# relay_controller.net
KiCad netlist of a schematic drawn in EAGLE
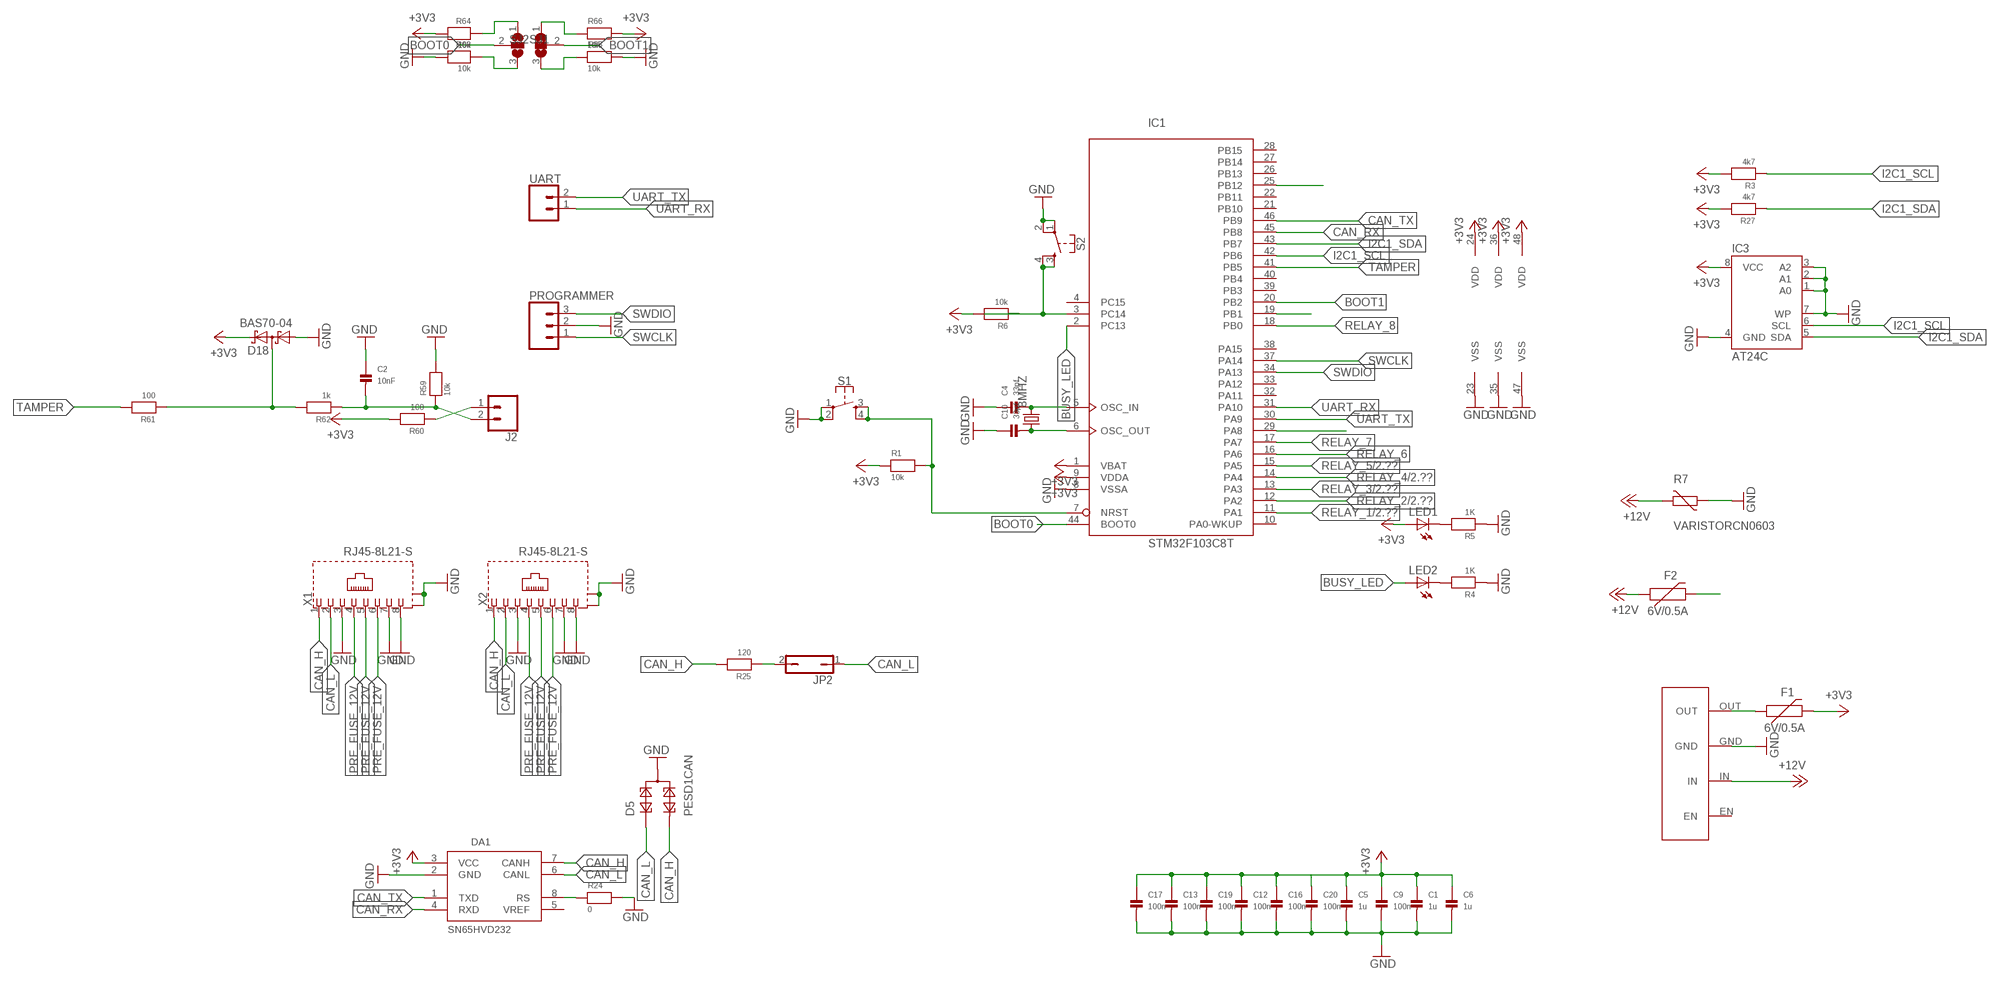
[diagram p0: schematic, sheet 1]
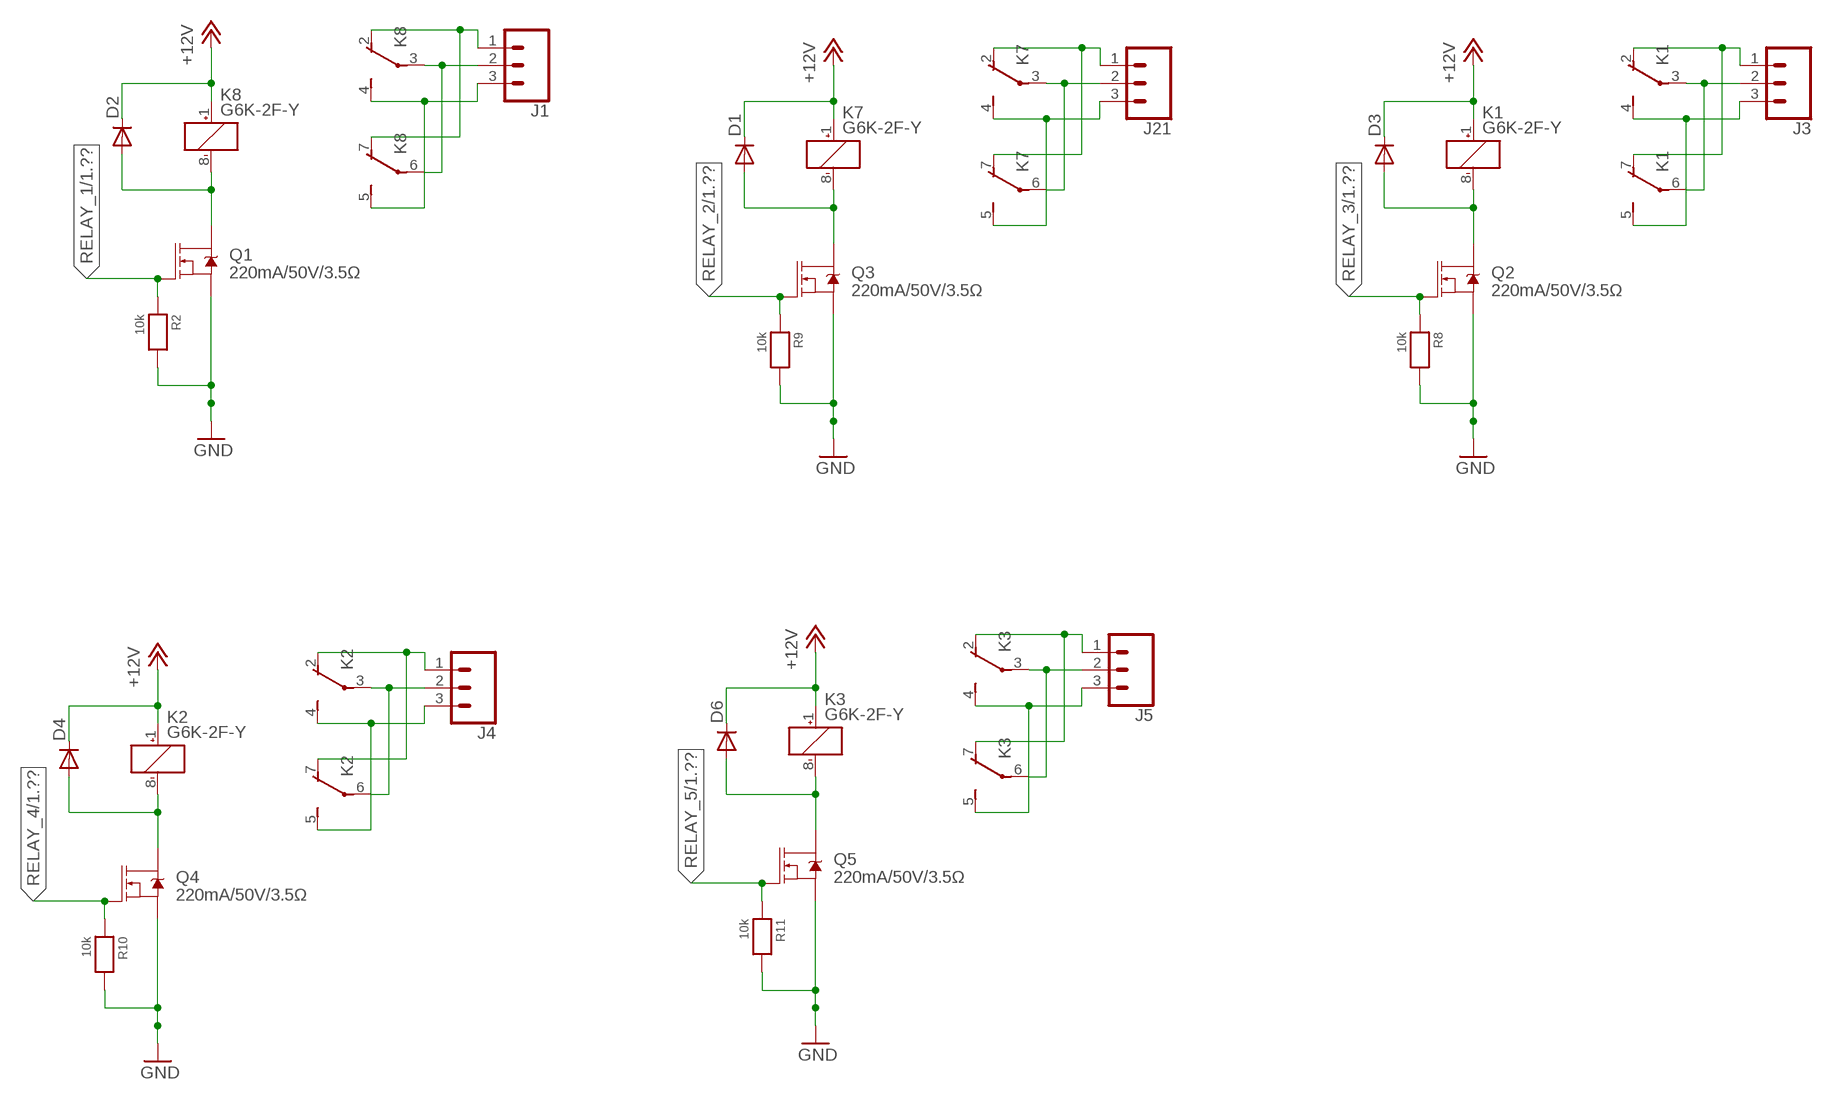
[diagram p1: schematic, sheet 2]

(export (version "E")
  (design (tool "Eeschema 10.0.6"))
  (components
    (comp (ref "D1")
      (value "DIODE-DO-214AC")
      (footprint "eagle-import:DO-214AC")
      (libsource (lib "eagle-import") (part "DIODE-DO-214AC"))
    )
    (comp (ref "D2")
      (value "DIODE-DO-214AC")
      (footprint "eagle-import:DO-214AC")
      (libsource (lib "eagle-import") (part "DIODE-DO-214AC"))
    )
    (comp (ref "D3")
      (value "DIODE-DO-214AC")
      (footprint "eagle-import:DO-214AC")
      (libsource (lib "eagle-import") (part "DIODE-DO-214AC"))
    )
    (comp (ref "D4")
      (value "DIODE-DO-214AC")
      (footprint "eagle-import:DO-214AC")
      (libsource (lib "eagle-import") (part "DIODE-DO-214AC"))
    )
    (comp (ref "D6")
      (value "DIODE-DO-214AC")
      (footprint "eagle-import:DO-214AC")
      (libsource (lib "eagle-import") (part "DIODE-DO-214AC"))
    )
    (comp (ref "J1")
      (value "CONN_03SCREW")
      (footprint "eagle-import:SCREWTERMINAL-3.5MM-3")
      (libsource (lib "eagle-import") (part "CONN_03SCREW"))
    )
    (comp (ref "J3")
      (value "CONN_03SCREW")
      (footprint "eagle-import:SCREWTERMINAL-3.5MM-3")
      (libsource (lib "eagle-import") (part "CONN_03SCREW"))
    )
    (comp (ref "J4")
      (value "CONN_03SCREW")
      (footprint "eagle-import:SCREWTERMINAL-3.5MM-3")
      (libsource (lib "eagle-import") (part "CONN_03SCREW"))
    )
    (comp (ref "J5")
      (value "CONN_03SCREW")
      (footprint "eagle-import:SCREWTERMINAL-3.5MM-3")
      (libsource (lib "eagle-import") (part "CONN_03SCREW"))
    )
    (comp (ref "J21")
      (value "CONN_03SCREW")
      (footprint "eagle-import:SCREWTERMINAL-3.5MM-3")
      (libsource (lib "eagle-import") (part "CONN_03SCREW"))
    )
    (comp (ref "K1")
      (value "G6K-2F-Y")
      (footprint "eagle-import:G6K-2F-Y")
      (fields (field (name "MF") "OMRON COMPONENTS USA") (field (name "MPN") "G6K-2F-Y DC3"))
      (libsource (lib "eagle-import") (part "G6K-2F-Y"))
    )
    (comp (ref "K2")
      (value "G6K-2F-Y")
      (footprint "eagle-import:G6K-2F-Y")
      (fields (field (name "MF") "OMRON COMPONENTS USA") (field (name "MPN") "G6K-2F-Y DC3"))
      (libsource (lib "eagle-import") (part "G6K-2F-Y"))
    )
    (comp (ref "K3")
      (value "G6K-2F-Y")
      (footprint "eagle-import:G6K-2F-Y")
      (fields (field (name "MF") "OMRON COMPONENTS USA") (field (name "MPN") "G6K-2F-Y DC3"))
      (libsource (lib "eagle-import") (part "G6K-2F-Y"))
    )
    (comp (ref "K7")
      (value "G6K-2F-Y")
      (footprint "eagle-import:G6K-2F-Y")
      (fields (field (name "MF") "OMRON COMPONENTS USA") (field (name "MPN") "G6K-2F-Y DC3"))
      (libsource (lib "eagle-import") (part "G6K-2F-Y"))
    )
    (comp (ref "K8")
      (value "G6K-2F-Y")
      (footprint "eagle-import:G6K-2F-Y")
      (fields (field (name "MF") "OMRON COMPONENTS USA") (field (name "MPN") "G6K-2F-Y DC3"))
      (libsource (lib "eagle-import") (part "G6K-2F-Y"))
    )
    (comp (ref "Q1")
      (value "220mA/50V/3.5Ω")
      (footprint "eagle-import:SOT23-3")
      (libsource (lib "eagle-import") (part "MOSFET-NCH-BSS138"))
    )
    (comp (ref "Q2")
      (value "220mA/50V/3.5Ω")
      (footprint "eagle-import:SOT23-3")
      (libsource (lib "eagle-import") (part "MOSFET-NCH-BSS138"))
    )
    (comp (ref "Q3")
      (value "220mA/50V/3.5Ω")
      (footprint "eagle-import:SOT23-3")
      (libsource (lib "eagle-import") (part "MOSFET-NCH-BSS138"))
    )
    (comp (ref "Q4")
      (value "220mA/50V/3.5Ω")
      (footprint "eagle-import:SOT23-3")
      (libsource (lib "eagle-import") (part "MOSFET-NCH-BSS138"))
    )
    (comp (ref "Q5")
      (value "220mA/50V/3.5Ω")
      (footprint "eagle-import:SOT23-3")
      (libsource (lib "eagle-import") (part "MOSFET-NCH-BSS138"))
    )
    (comp (ref "R2")
      (value "10k")
      (footprint "eagle-import:0603")
      (libsource (lib "eagle-import") (part "RESISTOR0603"))
    )
    (comp (ref "R8")
      (value "10k")
      (footprint "eagle-import:0603")
      (libsource (lib "eagle-import") (part "RESISTOR0603"))
    )
    (comp (ref "R9")
      (value "10k")
      (footprint "eagle-import:0603")
      (libsource (lib "eagle-import") (part "RESISTOR0603"))
    )
    (comp (ref "R10")
      (value "10k")
      (footprint "eagle-import:0603")
      (libsource (lib "eagle-import") (part "RESISTOR0603"))
    )
    (comp (ref "R11")
      (value "10k")
      (footprint "eagle-import:0603")
      (libsource (lib "eagle-import") (part "RESISTOR0603"))
    )
    (comp (ref "8MHZ")
      (value "CRYSTALHC49UP")
      (footprint "eagle-import:HC49UP")
      (libsource (lib "eagle-import") (part "CRYSTALHC49UP"))
    )
    (comp (ref "C1")
      (value "1u")
      (footprint "eagle-import:0603")
      (libsource (lib "eagle-import") (part "CAP_CERAMIC0603"))
    )
    (comp (ref "C2")
      (value "10nF")
      (footprint "eagle-import:0603")
      (libsource (lib "eagle-import") (part "CAP_CERAMIC0603"))
    )
    (comp (ref "C4")
      (value "33pf")
      (footprint "eagle-import:0603")
      (libsource (lib "eagle-import") (part "CAP_CERAMIC0603"))
    )
    (comp (ref "C5")
      (value "1u")
      (footprint "eagle-import:0603")
      (libsource (lib "eagle-import") (part "CAP_CERAMIC0603"))
    )
    (comp (ref "C6")
      (value "1u")
      (footprint "eagle-import:0603")
      (libsource (lib "eagle-import") (part "CAP_CERAMIC0603"))
    )
    (comp (ref "C9")
      (value "100n")
      (footprint "eagle-import:0603")
      (libsource (lib "eagle-import") (part "CAP_CERAMIC0603"))
    )
    (comp (ref "C10")
      (value "33pf")
      (footprint "eagle-import:0603")
      (libsource (lib "eagle-import") (part "CAP_CERAMIC0603"))
    )
    (comp (ref "C12")
      (value "100n")
      (footprint "eagle-import:0603")
      (libsource (lib "eagle-import") (part "CAP_CERAMIC0603"))
    )
    (comp (ref "C13")
      (value "100n")
      (footprint "eagle-import:0603")
      (libsource (lib "eagle-import") (part "CAP_CERAMIC0603"))
    )
    (comp (ref "C16")
      (value "100n")
      (footprint "eagle-import:0603")
      (libsource (lib "eagle-import") (part "CAP_CERAMIC0603"))
    )
    (comp (ref "C17")
      (value "100n")
      (footprint "eagle-import:0603")
      (libsource (lib "eagle-import") (part "CAP_CERAMIC0603"))
    )
    (comp (ref "C19")
      (value "100n")
      (footprint "eagle-import:0603")
      (libsource (lib "eagle-import") (part "CAP_CERAMIC0603"))
    )
    (comp (ref "C20")
      (value "100n")
      (footprint "eagle-import:0603")
      (libsource (lib "eagle-import") (part "CAP_CERAMIC0603"))
    )
    (comp (ref "D5")
      (value "PESD1CAN")
      (footprint "eagle-import:SOT23")
      (libsource (lib "eagle-import") (part "PESD1CAN"))
    )
    (comp (ref "D18")
      (value "BAS70-04")
      (footprint "eagle-import:SOT23")
      (libsource (lib "eagle-import") (part "BAS70-04"))
    )
    (comp (ref "DA1")
      (value "SN65HVD232")
      (footprint "eagle-import:SO08")
      (libsource (lib "eagle-import") (part "SN65HVD232"))
    )
    (comp (ref "F1")
      (value "6V/0.5A")
      (footprint "eagle-import:1206")
      (libsource (lib "eagle-import") (part "PPTC_HALF-AMP"))
    )
    (comp (ref "F2")
      (value "6V/0.5A")
      (footprint "eagle-import:1206")
      (libsource (lib "eagle-import") (part "PPTC_HALF-AMP"))
    )
    (comp (ref "IC1")
      (value "STM32F103C8T")
      (footprint "eagle-import:LQFP48")
      (libsource (lib "eagle-import") (part "STM32F103CT8"))
    )
    (comp (ref "IC3")
      (value "AT24C")
      (footprint "eagle-import:SOIC8")
      (libsource (lib "eagle-import") (part "AT24C"))
    )
    (comp (ref "J2")
      (value "CONN_023.5MM")
      (footprint "eagle-import:SCREWTERMINAL-3.5MM-2")
      (libsource (lib "eagle-import") (part "CONN_023.5MM"))
    )
    (comp (ref "JP2")
      (value "JP1Q")
      (footprint "eagle-import:JP1")
      (libsource (lib "eagle-import") (part "JP1Q"))
    )
    (comp (ref "LED1")
      (value "LEDCHIPLED_0805")
      (footprint "eagle-import:CHIPLED_0805")
      (libsource (lib "eagle-import") (part "LEDCHIPLED_0805"))
    )
    (comp (ref "LED2")
      (value "LEDCHIPLED_0805")
      (footprint "eagle-import:CHIPLED_0805")
      (libsource (lib "eagle-import") (part "LEDCHIPLED_0805"))
    )
    (comp (ref "PROGRAMMER")
      (value "CONN_03LOCK")
      (footprint "eagle-import:1X03_LOCK")
      (libsource (lib "eagle-import") (part "CONN_03LOCK"))
    )
    (comp (ref "R1")
      (value "10k")
      (footprint "eagle-import:0603")
      (libsource (lib "eagle-import") (part "RESISTOR0603"))
    )
    (comp (ref "R3")
      (value "4k7")
      (footprint "eagle-import:0603")
      (libsource (lib "eagle-import") (part "RESISTOR0603"))
    )
    (comp (ref "R4")
      (value "1K")
      (footprint "eagle-import:0603")
      (libsource (lib "eagle-import") (part "RESISTOR0603"))
    )
    (comp (ref "R5")
      (value "1K")
      (footprint "eagle-import:0603")
      (libsource (lib "eagle-import") (part "RESISTOR0603"))
    )
    (comp (ref "R6")
      (value "10k")
      (footprint "eagle-import:0603")
      (libsource (lib "eagle-import") (part "RESISTOR0603"))
    )
    (comp (ref "R7")
      (value "VARISTORCN0603")
      (footprint "eagle-import:CT_CN0603")
      (libsource (lib "eagle-import") (part "VARISTORCN0603"))
    )
    (comp (ref "R24")
      (value "0")
      (footprint "eagle-import:0603")
      (libsource (lib "eagle-import") (part "RESISTOR0603"))
    )
    (comp (ref "R25")
      (value "120")
      (footprint "eagle-import:0603")
      (libsource (lib "eagle-import") (part "RESISTOR0603"))
    )
    (comp (ref "R27")
      (value "4k7")
      (footprint "eagle-import:0603")
      (libsource (lib "eagle-import") (part "RESISTOR0603"))
    )
    (comp (ref "R59")
      (value "10k")
      (footprint "eagle-import:0603")
      (libsource (lib "eagle-import") (part "RESISTOR0603"))
    )
    (comp (ref "R60")
      (value "100")
      (footprint "eagle-import:0603")
      (libsource (lib "eagle-import") (part "RESISTOR0603"))
    )
    (comp (ref "R61")
      (value "100")
      (footprint "eagle-import:0603")
      (libsource (lib "eagle-import") (part "RESISTOR0603"))
    )
    (comp (ref "R62")
      (value "1k")
      (footprint "eagle-import:0603")
      (libsource (lib "eagle-import") (part "RESISTOR0603"))
    )
    (comp (ref "R63")
      (value "10k")
      (footprint "eagle-import:0603")
      (libsource (lib "eagle-import") (part "RESISTOR0603"))
    )
    (comp (ref "R64")
      (value "10k")
      (footprint "eagle-import:0603")
      (libsource (lib "eagle-import") (part "RESISTOR0603"))
    )
    (comp (ref "R65")
      (value "10k")
      (footprint "eagle-import:0603")
      (libsource (lib "eagle-import") (part "RESISTOR0603"))
    )
    (comp (ref "R66")
      (value "10k")
      (footprint "eagle-import:0603")
      (libsource (lib "eagle-import") (part "RESISTOR0603"))
    )
    (comp (ref "S1")
      (value "MOMENTARY-SWITCH-SPST-2-SMD-4.6X2.8MM")
      (footprint "eagle-import:TACTILE_SWITCH_SMD_4.6X2.8MM")
      (libsource (lib "eagle-import") (part "MOMENTARY-SWITCH-SPST-2-SMD-4.6X2.8MM"))
    )
    (comp (ref "S2")
      (value "MOMENTARY-SWITCH-SPST-2-SMD-4.6X2.8MM")
      (footprint "eagle-import:TACTILE_SWITCH_SMD_4.6X2.8MM")
      (libsource (lib "eagle-import") (part "MOMENTARY-SWITCH-SPST-2-SMD-4.6X2.8MM"))
    )
    (comp (ref "SJ1")
      (value "SJ2W")
      (footprint "eagle-import:SJ_2")
      (libsource (lib "eagle-import") (part "SJ2W"))
    )
    (comp (ref "SJ2")
      (value "SJ2W")
      (footprint "eagle-import:SJ_2")
      (libsource (lib "eagle-import") (part "SJ2W"))
    )
    (comp (ref "U$1")
      (value "HW-613")
      (footprint "eagle-import:HW-613")
      (libsource (lib "eagle-import") (part "HW-613"))
    )
    (comp (ref "UART")
      (value "CONN_02")
      (footprint "eagle-import:1X02")
      (libsource (lib "eagle-import") (part "CONN_02"))
    )
    (comp (ref "X1")
      (value "RJ45-8L21-S")
      (footprint "eagle-import:RJ45-SHIELD1")
      (libsource (lib "eagle-import") (part "RJ4521-S-8L"))
    )
    (comp (ref "X2")
      (value "RJ45-8L21-S")
      (footprint "eagle-import:RJ45-SHIELD1")
      (libsource (lib "eagle-import") (part "RJ4521-S-8L"))
    )
  )
  (nets
    (net (code "1") (name "+3V3") (class "Default")
      (node (ref "C1") (pin "1") (pinfunction "P$1_1") (pintype "passive"))
      (node (ref "C12") (pin "1") (pinfunction "P$1_1") (pintype "passive"))
      (node (ref "C13") (pin "1") (pinfunction "P$1_1") (pintype "passive"))
      (node (ref "C16") (pin "1") (pinfunction "P$1_1") (pintype "passive"))
      (node (ref "C17") (pin "1") (pinfunction "P$1_1") (pintype "passive"))
      (node (ref "C19") (pin "1") (pinfunction "P$1_1") (pintype "passive"))
      (node (ref "C20") (pin "1") (pinfunction "P$1_1") (pintype "passive"))
      (node (ref "C5") (pin "1") (pinfunction "P$1_1") (pintype "passive"))
      (node (ref "C6") (pin "1") (pinfunction "P$1_1") (pintype "passive"))
      (node (ref "C9") (pin "1") (pinfunction "P$1_1") (pintype "passive"))
      (node (ref "D18") (pin "2") (pinfunction "C2_2") (pintype "passive"))
      (node (ref "DA1") (pin "3") (pinfunction "VCC_3") (pintype "power_in"))
      (node (ref "F1") (pin "2") (pinfunction "2_2") (pintype "bidirectional"))
      (node (ref "IC1") (pin "1") (pinfunction "VBAT_1") (pintype "power_in"))
      (node (ref "IC1") (pin "24") (pinfunction "VDD_24") (pintype "power_in"))
      (node (ref "IC1") (pin "36") (pinfunction "VDD_36") (pintype "power_in"))
      (node (ref "IC1") (pin "48") (pinfunction "VDD_48") (pintype "power_in"))
      (node (ref "IC1") (pin "9") (pinfunction "VDDA_9") (pintype "power_in"))
      (node (ref "IC3") (pin "8") (pinfunction "VCC_8") (pintype "power_in"))
      (node (ref "LED1") (pin "A") (pinfunction "A_A") (pintype "passive"))
      (node (ref "R1") (pin "1") (pinfunction "1_1") (pintype "passive"))
      (node (ref "R27") (pin "2") (pinfunction "2_2") (pintype "passive"))
      (node (ref "R3") (pin "2") (pinfunction "2_2") (pintype "passive"))
      (node (ref "R6") (pin "2") (pinfunction "2_2") (pintype "passive"))
      (node (ref "R60") (pin "2") (pinfunction "2_2") (pintype "passive"))
      (node (ref "R64") (pin "2") (pinfunction "2_2") (pintype "passive"))
      (node (ref "R66") (pin "2") (pinfunction "2_2") (pintype "passive"))
    )
    (net (code "2") (name "+12V") (class "Default")
      (node (ref "D1") (pin "C") (pinfunction "C_C") (pintype "passive"))
      (node (ref "D2") (pin "C") (pinfunction "C_C") (pintype "passive"))
      (node (ref "D3") (pin "C") (pinfunction "C_C") (pintype "passive"))
      (node (ref "D4") (pin "C") (pinfunction "C_C") (pintype "passive"))
      (node (ref "D6") (pin "C") (pinfunction "C_C") (pintype "passive"))
      (node (ref "F2") (pin "1") (pinfunction "1_1") (pintype "bidirectional"))
      (node (ref "K1") (pin "1") (pinfunction "+_1") (pintype "passive"))
      (node (ref "K2") (pin "1") (pinfunction "+_1") (pintype "passive"))
      (node (ref "K3") (pin "1") (pinfunction "+_1") (pintype "passive"))
      (node (ref "K7") (pin "1") (pinfunction "+_1") (pintype "passive"))
      (node (ref "K8") (pin "1") (pinfunction "+_1") (pintype "passive"))
      (node (ref "R7") (pin "2") (pinfunction "2_2") (pintype "passive"))
      (node (ref "U$1") (pin "IN") (pinfunction "IN_IN") (pintype "bidirectional"))
    )
    (net (code "3") (name "BOOT0") (class "Default")
      (node (ref "IC1") (pin "44") (pinfunction "BOOT0_44") (pintype "input"))
      (node (ref "SJ1") (pin "2") (pinfunction "2_2") (pintype "passive"))
    )
    (net (code "4") (name "BOOT1") (class "Default")
      (node (ref "IC1") (pin "20") (pinfunction "PB2_20") (pintype "bidirectional"))
      (node (ref "SJ2") (pin "2") (pinfunction "2_2") (pintype "passive"))
    )
    (net (code "5") (name "BUSY_LED") (class "Default")
      (node (ref "IC1") (pin "2") (pinfunction "PC13_2") (pintype "bidirectional"))
      (node (ref "LED2") (pin "A") (pinfunction "A_A") (pintype "passive"))
    )
    (net (code "6") (name "CAN_H") (class "Default")
      (node (ref "D5") (pin "2") (pinfunction "2_2") (pintype "passive"))
      (node (ref "DA1") (pin "7") (pinfunction "CANH_7") (pintype "bidirectional"))
      (node (ref "R25") (pin "2") (pinfunction "2_2") (pintype "passive"))
      (node (ref "X1") (pin "1") (pinfunction "1_1") (pintype "passive"))
      (node (ref "X2") (pin "1") (pinfunction "1_1") (pintype "passive"))
    )
    (net (code "7") (name "CAN_L") (class "Default")
      (node (ref "D5") (pin "1") (pinfunction "1_1") (pintype "passive"))
      (node (ref "DA1") (pin "6") (pinfunction "CANL_6") (pintype "bidirectional"))
      (node (ref "JP2") (pin "1") (pinfunction "1_1") (pintype "passive"))
      (node (ref "X1") (pin "2") (pinfunction "2_2") (pintype "passive"))
      (node (ref "X2") (pin "2") (pinfunction "2_2") (pintype "passive"))
    )
    (net (code "8") (name "CAN_RX") (class "Default")
      (node (ref "DA1") (pin "4") (pinfunction "RXD_4") (pintype "output"))
      (node (ref "IC1") (pin "45") (pinfunction "PB8_45") (pintype "bidirectional"))
    )
    (net (code "9") (name "CAN_TX") (class "Default")
      (node (ref "DA1") (pin "1") (pinfunction "TXD_1") (pintype "input"))
      (node (ref "IC1") (pin "46") (pinfunction "PB9_46") (pintype "bidirectional"))
    )
    (net (code "10") (name "GND") (class "Default")
      (node (ref "C1") (pin "2") (pinfunction "P$2_2") (pintype "passive"))
      (node (ref "C10") (pin "1") (pinfunction "P$1_1") (pintype "passive"))
      (node (ref "C12") (pin "2") (pinfunction "P$2_2") (pintype "passive"))
      (node (ref "C13") (pin "2") (pinfunction "P$2_2") (pintype "passive"))
      (node (ref "C16") (pin "2") (pinfunction "P$2_2") (pintype "passive"))
      (node (ref "C17") (pin "2") (pinfunction "P$2_2") (pintype "passive"))
      (node (ref "C19") (pin "2") (pinfunction "P$2_2") (pintype "passive"))
      (node (ref "C2") (pin "1") (pinfunction "P$1_1") (pintype "passive"))
      (node (ref "C20") (pin "2") (pinfunction "P$2_2") (pintype "passive"))
      (node (ref "C4") (pin "1") (pinfunction "P$1_1") (pintype "passive"))
      (node (ref "C5") (pin "2") (pinfunction "P$2_2") (pintype "passive"))
      (node (ref "C6") (pin "2") (pinfunction "P$2_2") (pintype "passive"))
      (node (ref "C9") (pin "2") (pinfunction "P$2_2") (pintype "passive"))
      (node (ref "D18") (pin "1") (pinfunction "A1_1") (pintype "passive"))
      (node (ref "D5") (pin "3") (pinfunction "3_3") (pintype "passive"))
      (node (ref "DA1") (pin "2") (pinfunction "GND_2") (pintype "power_in"))
      (node (ref "IC1") (pin "23") (pinfunction "VSS_23") (pintype "power_in"))
      (node (ref "IC1") (pin "35") (pinfunction "VSS_35") (pintype "power_in"))
      (node (ref "IC1") (pin "47") (pinfunction "VSS_47") (pintype "power_in"))
      (node (ref "IC1") (pin "8") (pinfunction "VSSA_8") (pintype "power_in"))
      (node (ref "IC3") (pin "1") (pinfunction "A0_1") (pintype "input"))
      (node (ref "IC3") (pin "2") (pinfunction "A1_2") (pintype "input"))
      (node (ref "IC3") (pin "3") (pinfunction "A2_3") (pintype "input"))
      (node (ref "IC3") (pin "4") (pinfunction "GND_4") (pintype "power_in"))
      (node (ref "IC3") (pin "7") (pinfunction "WP_7") (pintype "input"))
      (node (ref "PROGRAMMER") (pin "2") (pinfunction "2_2") (pintype "passive"))
      (node (ref "Q1") (pin "2") (pinfunction "S_2") (pintype "bidirectional"))
      (node (ref "Q2") (pin "2") (pinfunction "S_2") (pintype "bidirectional"))
      (node (ref "Q3") (pin "2") (pinfunction "S_2") (pintype "bidirectional"))
      (node (ref "Q4") (pin "2") (pinfunction "S_2") (pintype "bidirectional"))
      (node (ref "Q5") (pin "2") (pinfunction "S_2") (pintype "bidirectional"))
      (node (ref "R10") (pin "2") (pinfunction "2_2") (pintype "passive"))
      (node (ref "R11") (pin "2") (pinfunction "2_2") (pintype "passive"))
      (node (ref "R2") (pin "2") (pinfunction "2_2") (pintype "passive"))
      (node (ref "R24") (pin "2") (pinfunction "2_2") (pintype "passive"))
      (node (ref "R4") (pin "1") (pinfunction "1_1") (pintype "passive"))
      (node (ref "R5") (pin "1") (pinfunction "1_1") (pintype "passive"))
      (node (ref "R59") (pin "2") (pinfunction "2_2") (pintype "passive"))
      (node (ref "R63") (pin "2") (pinfunction "2_2") (pintype "passive"))
      (node (ref "R65") (pin "2") (pinfunction "2_2") (pintype "passive"))
      (node (ref "R7") (pin "1") (pinfunction "1_1") (pintype "passive"))
      (node (ref "R8") (pin "2") (pinfunction "2_2") (pintype "passive"))
      (node (ref "R9") (pin "2") (pinfunction "2_2") (pintype "passive"))
      (node (ref "S1") (pin "1") (pinfunction "1_1") (pintype "passive"))
      (node (ref "S1") (pin "2") (pinfunction "2_2") (pintype "passive"))
      (node (ref "S2") (pin "1") (pinfunction "1_1") (pintype "passive"))
      (node (ref "S2") (pin "2") (pinfunction "2_2") (pintype "passive"))
      (node (ref "U$1") (pin "GND") (pinfunction "GND_GND") (pintype "bidirectional"))
      (node (ref "X1") (pin "3") (pinfunction "3_3") (pintype "passive"))
      (node (ref "X1") (pin "7") (pinfunction "7_7") (pintype "passive"))
      (node (ref "X1") (pin "8") (pinfunction "8_8") (pintype "passive"))
      (node (ref "X1") (pin "S1") (pinfunction "S_S1") (pintype "passive"))
      (node (ref "X1") (pin "S2") (pinfunction "S_S2") (pintype "passive"))
      (node (ref "X2") (pin "3") (pinfunction "3_3") (pintype "passive"))
      (node (ref "X2") (pin "7") (pinfunction "7_7") (pintype "passive"))
      (node (ref "X2") (pin "8") (pinfunction "8_8") (pintype "passive"))
      (node (ref "X2") (pin "S1") (pinfunction "S_S1") (pintype "passive"))
      (node (ref "X2") (pin "S2") (pinfunction "S_S2") (pintype "passive"))
    )
    (net (code "11") (name "I2C1_SCL") (class "Default")
      (node (ref "IC1") (pin "42") (pinfunction "PB6_42") (pintype "bidirectional"))
      (node (ref "IC3") (pin "6") (pinfunction "SCL_6") (pintype "bidirectional"))
      (node (ref "R3") (pin "1") (pinfunction "1_1") (pintype "passive"))
    )
    (net (code "12") (name "I2C1_SDA") (class "Default")
      (node (ref "IC1") (pin "43") (pinfunction "PB7_43") (pintype "bidirectional"))
      (node (ref "IC3") (pin "5") (pinfunction "SDA_5") (pintype "bidirectional"))
      (node (ref "R27") (pin "1") (pinfunction "1_1") (pintype "passive"))
    )
    (net (code "13") (name "Net-(C2-P$2)") (class "Default")
      (node (ref "C2") (pin "2") (pinfunction "P$2_2") (pintype "passive"))
      (node (ref "J2") (pin "2") (pinfunction "2_2") (pintype "passive"))
      (node (ref "R59") (pin "1") (pinfunction "1_1") (pintype "passive"))
      (node (ref "R62") (pin "1") (pinfunction "1_1") (pintype "passive"))
    )
    (net (code "14") (name "Net-(C4-P$2)") (class "Default")
      (node (ref "8MHZ") (pin "2") (pinfunction "2_2") (pintype "passive"))
      (node (ref "C4") (pin "2") (pinfunction "P$2_2") (pintype "passive"))
      (node (ref "IC1") (pin "5") (pinfunction "OSC_IN_5") (pintype "bidirectional"))
    )
    (net (code "15") (name "Net-(C10-P$2)") (class "Default")
      (node (ref "8MHZ") (pin "1") (pinfunction "1_1") (pintype "passive"))
      (node (ref "C10") (pin "2") (pinfunction "P$2_2") (pintype "passive"))
      (node (ref "IC1") (pin "6") (pinfunction "OSC_OUT_6") (pintype "bidirectional"))
    )
    (net (code "16") (name "Net-(D18-C1A2)") (class "Default")
      (node (ref "D18") (pin "3") (pinfunction "C1A2_3") (pintype "passive"))
      (node (ref "R61") (pin "1") (pinfunction "1_1") (pintype "passive"))
      (node (ref "R62") (pin "2") (pinfunction "2_2") (pintype "passive"))
    )
    (net (code "17") (name "Net-(DA1-RS)") (class "Default")
      (node (ref "DA1") (pin "8") (pinfunction "RS_8") (pintype "bidirectional"))
      (node (ref "R24") (pin "1") (pinfunction "1_1") (pintype "passive"))
    )
    (net (code "18") (name "Net-(F1-Pad1)") (class "Default")
      (node (ref "F1") (pin "1") (pinfunction "1_1") (pintype "bidirectional"))
      (node (ref "U$1") (pin "OUT") (pinfunction "OUT_OUT") (pintype "bidirectional"))
    )
    (net (code "19") (name "Net-(IC1A-NRST)") (class "Default")
      (node (ref "IC1") (pin "7") (pinfunction "NRST_7") (pintype "bidirectional"))
      (node (ref "R1") (pin "2") (pinfunction "2_2") (pintype "passive"))
      (node (ref "S1") (pin "3") (pinfunction "3_3") (pintype "passive"))
      (node (ref "S1") (pin "4") (pinfunction "4_4") (pintype "passive"))
    )
    (net (code "20") (name "Net-(IC1A-PC14)") (class "Default")
      (node (ref "IC1") (pin "3") (pinfunction "PC14_3") (pintype "bidirectional"))
      (node (ref "R6") (pin "1") (pinfunction "1_1") (pintype "passive"))
      (node (ref "S2") (pin "3") (pinfunction "3_3") (pintype "passive"))
      (node (ref "S2") (pin "4") (pinfunction "4_4") (pintype "passive"))
    )
    (net (code "21") (name "Net-(J2-Pad1)") (class "Default")
      (node (ref "J2") (pin "1") (pinfunction "1_1") (pintype "passive"))
      (node (ref "R60") (pin "1") (pinfunction "1_1") (pintype "passive"))
    )
    (net (code "22") (name "Net-(JP2-Pad2)") (class "Default")
      (node (ref "JP2") (pin "2") (pinfunction "2_2") (pintype "passive"))
      (node (ref "R25") (pin "1") (pinfunction "1_1") (pintype "passive"))
    )
    (net (code "23") (name "Net-(K1A--)") (class "Default")
      (node (ref "D3") (pin "A") (pinfunction "A_A") (pintype "passive"))
      (node (ref "K1") (pin "8") (pinfunction "-_8") (pintype "passive"))
      (node (ref "Q2") (pin "3") (pinfunction "D_3") (pintype "bidirectional"))
    )
    (net (code "24") (name "Net-(K1B-O)") (class "Default")
      (node (ref "J3") (pin "1") (pinfunction "1_1") (pintype "passive"))
      (node (ref "K1") (pin "2") (pinfunction "O_2") (pintype "passive"))
      (node (ref "K1") (pin "7") (pinfunction "O_7") (pintype "passive"))
    )
    (net (code "25") (name "Net-(K1B-P)") (class "Default")
      (node (ref "J3") (pin "2") (pinfunction "2_2") (pintype "passive"))
      (node (ref "K1") (pin "3") (pinfunction "P_3") (pintype "passive"))
      (node (ref "K1") (pin "6") (pinfunction "P_6") (pintype "passive"))
    )
    (net (code "26") (name "Net-(K1B-S)") (class "Default")
      (node (ref "J3") (pin "3") (pinfunction "3_3") (pintype "passive"))
      (node (ref "K1") (pin "4") (pinfunction "S_4") (pintype "passive"))
      (node (ref "K1") (pin "5") (pinfunction "S_5") (pintype "passive"))
    )
    (net (code "27") (name "Net-(K2A--)") (class "Default")
      (node (ref "D4") (pin "A") (pinfunction "A_A") (pintype "passive"))
      (node (ref "K2") (pin "8") (pinfunction "-_8") (pintype "passive"))
      (node (ref "Q4") (pin "3") (pinfunction "D_3") (pintype "bidirectional"))
    )
    (net (code "28") (name "Net-(K2B-O)") (class "Default")
      (node (ref "J4") (pin "1") (pinfunction "1_1") (pintype "passive"))
      (node (ref "K2") (pin "2") (pinfunction "O_2") (pintype "passive"))
      (node (ref "K2") (pin "7") (pinfunction "O_7") (pintype "passive"))
    )
    (net (code "29") (name "Net-(K2B-P)") (class "Default")
      (node (ref "J4") (pin "2") (pinfunction "2_2") (pintype "passive"))
      (node (ref "K2") (pin "3") (pinfunction "P_3") (pintype "passive"))
      (node (ref "K2") (pin "6") (pinfunction "P_6") (pintype "passive"))
    )
    (net (code "30") (name "Net-(K2B-S)") (class "Default")
      (node (ref "J4") (pin "3") (pinfunction "3_3") (pintype "passive"))
      (node (ref "K2") (pin "4") (pinfunction "S_4") (pintype "passive"))
      (node (ref "K2") (pin "5") (pinfunction "S_5") (pintype "passive"))
    )
    (net (code "31") (name "Net-(K3A--)") (class "Default")
      (node (ref "D6") (pin "A") (pinfunction "A_A") (pintype "passive"))
      (node (ref "K3") (pin "8") (pinfunction "-_8") (pintype "passive"))
      (node (ref "Q5") (pin "3") (pinfunction "D_3") (pintype "bidirectional"))
    )
    (net (code "32") (name "Net-(K3B-O)") (class "Default")
      (node (ref "J5") (pin "1") (pinfunction "1_1") (pintype "passive"))
      (node (ref "K3") (pin "2") (pinfunction "O_2") (pintype "passive"))
      (node (ref "K3") (pin "7") (pinfunction "O_7") (pintype "passive"))
    )
    (net (code "33") (name "Net-(K3B-P)") (class "Default")
      (node (ref "J5") (pin "2") (pinfunction "2_2") (pintype "passive"))
      (node (ref "K3") (pin "3") (pinfunction "P_3") (pintype "passive"))
      (node (ref "K3") (pin "6") (pinfunction "P_6") (pintype "passive"))
    )
    (net (code "34") (name "Net-(K3B-S)") (class "Default")
      (node (ref "J5") (pin "3") (pinfunction "3_3") (pintype "passive"))
      (node (ref "K3") (pin "4") (pinfunction "S_4") (pintype "passive"))
      (node (ref "K3") (pin "5") (pinfunction "S_5") (pintype "passive"))
    )
    (net (code "35") (name "Net-(K7A--)") (class "Default")
      (node (ref "D1") (pin "A") (pinfunction "A_A") (pintype "passive"))
      (node (ref "K7") (pin "8") (pinfunction "-_8") (pintype "passive"))
      (node (ref "Q3") (pin "3") (pinfunction "D_3") (pintype "bidirectional"))
    )
    (net (code "36") (name "Net-(K7B-O)") (class "Default")
      (node (ref "J21") (pin "1") (pinfunction "1_1") (pintype "passive"))
      (node (ref "K7") (pin "2") (pinfunction "O_2") (pintype "passive"))
      (node (ref "K7") (pin "7") (pinfunction "O_7") (pintype "passive"))
    )
    (net (code "37") (name "Net-(K7B-P)") (class "Default")
      (node (ref "J21") (pin "2") (pinfunction "2_2") (pintype "passive"))
      (node (ref "K7") (pin "3") (pinfunction "P_3") (pintype "passive"))
      (node (ref "K7") (pin "6") (pinfunction "P_6") (pintype "passive"))
    )
    (net (code "38") (name "Net-(K7B-S)") (class "Default")
      (node (ref "J21") (pin "3") (pinfunction "3_3") (pintype "passive"))
      (node (ref "K7") (pin "4") (pinfunction "S_4") (pintype "passive"))
      (node (ref "K7") (pin "5") (pinfunction "S_5") (pintype "passive"))
    )
    (net (code "39") (name "Net-(K8A--)") (class "Default")
      (node (ref "D2") (pin "A") (pinfunction "A_A") (pintype "passive"))
      (node (ref "K8") (pin "8") (pinfunction "-_8") (pintype "passive"))
      (node (ref "Q1") (pin "3") (pinfunction "D_3") (pintype "bidirectional"))
    )
    (net (code "40") (name "Net-(K8B-O)") (class "Default")
      (node (ref "J1") (pin "1") (pinfunction "1_1") (pintype "passive"))
      (node (ref "K8") (pin "2") (pinfunction "O_2") (pintype "passive"))
      (node (ref "K8") (pin "7") (pinfunction "O_7") (pintype "passive"))
    )
    (net (code "41") (name "Net-(K8B-P)") (class "Default")
      (node (ref "J1") (pin "2") (pinfunction "2_2") (pintype "passive"))
      (node (ref "K8") (pin "3") (pinfunction "P_3") (pintype "passive"))
      (node (ref "K8") (pin "6") (pinfunction "P_6") (pintype "passive"))
    )
    (net (code "42") (name "Net-(K8B-S)") (class "Default")
      (node (ref "J1") (pin "3") (pinfunction "3_3") (pintype "passive"))
      (node (ref "K8") (pin "4") (pinfunction "S_4") (pintype "passive"))
      (node (ref "K8") (pin "5") (pinfunction "S_5") (pintype "passive"))
    )
    (net (code "43") (name "Net-(LED1-PadC)") (class "Default")
      (node (ref "LED1") (pin "C") (pinfunction "C_C") (pintype "passive"))
      (node (ref "R5") (pin "2") (pinfunction "2_2") (pintype "passive"))
    )
    (net (code "44") (name "Net-(LED2-PadC)") (class "Default")
      (node (ref "LED2") (pin "C") (pinfunction "C_C") (pintype "passive"))
      (node (ref "R4") (pin "2") (pinfunction "2_2") (pintype "passive"))
    )
    (net (code "45") (name "Net-(R63-Pad1)") (class "Default")
      (node (ref "R63") (pin "1") (pinfunction "1_1") (pintype "passive"))
      (node (ref "SJ1") (pin "3") (pinfunction "3_3") (pintype "passive"))
    )
    (net (code "46") (name "Net-(R64-Pad1)") (class "Default")
      (node (ref "R64") (pin "1") (pinfunction "1_1") (pintype "passive"))
      (node (ref "SJ1") (pin "1") (pinfunction "1_1") (pintype "passive"))
    )
    (net (code "47") (name "Net-(R65-Pad1)") (class "Default")
      (node (ref "R65") (pin "1") (pinfunction "1_1") (pintype "passive"))
      (node (ref "SJ2") (pin "3") (pinfunction "3_3") (pintype "passive"))
    )
    (net (code "48") (name "Net-(R66-Pad1)") (class "Default")
      (node (ref "R66") (pin "1") (pinfunction "1_1") (pintype "passive"))
      (node (ref "SJ2") (pin "1") (pinfunction "1_1") (pintype "passive"))
    )
    (net (code "49") (name "PRE_FUSE_12V") (class "Default")
      (node (ref "F2") (pin "2") (pinfunction "2_2") (pintype "bidirectional"))
      (node (ref "X1") (pin "4") (pinfunction "4_4") (pintype "passive"))
      (node (ref "X1") (pin "5") (pinfunction "5_5") (pintype "passive"))
      (node (ref "X1") (pin "6") (pinfunction "6_6") (pintype "passive"))
      (node (ref "X2") (pin "4") (pinfunction "4_4") (pintype "passive"))
      (node (ref "X2") (pin "5") (pinfunction "5_5") (pintype "passive"))
      (node (ref "X2") (pin "6") (pinfunction "6_6") (pintype "passive"))
    )
    (net (code "50") (name "RELAY_1") (class "Default")
      (node (ref "IC1") (pin "11") (pinfunction "PA1_11") (pintype "bidirectional"))
      (node (ref "Q1") (pin "1") (pinfunction "G_1") (pintype "bidirectional"))
      (node (ref "R2") (pin "1") (pinfunction "1_1") (pintype "passive"))
    )
    (net (code "51") (name "RELAY_2") (class "Default")
      (node (ref "IC1") (pin "12") (pinfunction "PA2_12") (pintype "bidirectional"))
      (node (ref "Q3") (pin "1") (pinfunction "G_1") (pintype "bidirectional"))
      (node (ref "R9") (pin "1") (pinfunction "1_1") (pintype "passive"))
    )
    (net (code "52") (name "RELAY_3") (class "Default")
      (node (ref "IC1") (pin "13") (pinfunction "PA3_13") (pintype "bidirectional"))
      (node (ref "Q2") (pin "1") (pinfunction "G_1") (pintype "bidirectional"))
      (node (ref "R8") (pin "1") (pinfunction "1_1") (pintype "passive"))
    )
    (net (code "53") (name "RELAY_4") (class "Default")
      (node (ref "IC1") (pin "14") (pinfunction "PA4_14") (pintype "bidirectional"))
      (node (ref "Q4") (pin "1") (pinfunction "G_1") (pintype "bidirectional"))
      (node (ref "R10") (pin "1") (pinfunction "1_1") (pintype "passive"))
    )
    (net (code "54") (name "RELAY_5") (class "Default")
      (node (ref "IC1") (pin "15") (pinfunction "PA5_15") (pintype "bidirectional"))
      (node (ref "Q5") (pin "1") (pinfunction "G_1") (pintype "bidirectional"))
      (node (ref "R11") (pin "1") (pinfunction "1_1") (pintype "passive"))
    )
    (net (code "55") (name "RELAY_6") (class "Default")
      (node (ref "IC1") (pin "16") (pinfunction "PA6_16") (pintype "bidirectional"))
    )
    (net (code "56") (name "RELAY_7") (class "Default")
      (node (ref "IC1") (pin "17") (pinfunction "PA7_17") (pintype "bidirectional"))
    )
    (net (code "57") (name "RELAY_8") (class "Default")
      (node (ref "IC1") (pin "18") (pinfunction "PB0_18") (pintype "bidirectional"))
    )
    (net (code "58") (name "SWCLK") (class "Default")
      (node (ref "IC1") (pin "37") (pinfunction "PA14_37") (pintype "bidirectional"))
      (node (ref "PROGRAMMER") (pin "1") (pinfunction "1_1") (pintype "passive"))
    )
    (net (code "59") (name "SWDIO") (class "Default")
      (node (ref "IC1") (pin "34") (pinfunction "PA13_34") (pintype "bidirectional"))
      (node (ref "PROGRAMMER") (pin "3") (pinfunction "3_3") (pintype "passive"))
    )
    (net (code "60") (name "TAMPER") (class "Default")
      (node (ref "IC1") (pin "41") (pinfunction "PB5_41") (pintype "bidirectional"))
      (node (ref "R61") (pin "2") (pinfunction "2_2") (pintype "passive"))
    )
    (net (code "61") (name "UART_RX") (class "Default")
      (node (ref "IC1") (pin "31") (pinfunction "PA10_31") (pintype "bidirectional"))
      (node (ref "UART") (pin "1") (pinfunction "1_1") (pintype "passive"))
    )
    (net (code "62") (name "UART_TX") (class "Default")
      (node (ref "IC1") (pin "30") (pinfunction "PA9_30") (pintype "bidirectional"))
      (node (ref "UART") (pin "2") (pinfunction "2_2") (pintype "passive"))
    )
    (net (code "63") (name "unconnected-(DA1-VREF-Pad5)") (class "Default")
      (node (ref "DA1") (pin "5") (pinfunction "VREF_5") (pintype "bidirectional"))
    )
    (net (code "64") (name "unconnected-(IC1A-PA0-WKUP-Pad10)") (class "Default")
      (node (ref "IC1") (pin "10") (pinfunction "PA0-WKUP_10") (pintype "bidirectional"))
    )
    (net (code "65") (name "unconnected-(IC1A-PA8-Pad29)") (class "Default")
      (node (ref "IC1") (pin "29") (pinfunction "PA8_29") (pintype "bidirectional"))
    )
    (net (code "66") (name "unconnected-(IC1A-PA11-Pad32)") (class "Default")
      (node (ref "IC1") (pin "32") (pinfunction "PA11_32") (pintype "bidirectional"))
    )
    (net (code "67") (name "unconnected-(IC1A-PA12-Pad33)") (class "Default")
      (node (ref "IC1") (pin "33") (pinfunction "PA12_33") (pintype "bidirectional"))
    )
    (net (code "68") (name "unconnected-(IC1A-PA15-Pad38)") (class "Default")
      (node (ref "IC1") (pin "38") (pinfunction "PA15_38") (pintype "bidirectional"))
    )
    (net (code "69") (name "unconnected-(IC1A-PB1-Pad19)") (class "Default")
      (node (ref "IC1") (pin "19") (pinfunction "PB1_19") (pintype "bidirectional"))
    )
    (net (code "70") (name "unconnected-(IC1A-PB3-Pad39)") (class "Default")
      (node (ref "IC1") (pin "39") (pinfunction "PB3_39") (pintype "bidirectional"))
    )
    (net (code "71") (name "unconnected-(IC1A-PB4-Pad40)") (class "Default")
      (node (ref "IC1") (pin "40") (pinfunction "PB4_40") (pintype "bidirectional"))
    )
    (net (code "72") (name "unconnected-(IC1A-PB10-Pad21)") (class "Default")
      (node (ref "IC1") (pin "21") (pinfunction "PB10_21") (pintype "bidirectional"))
    )
    (net (code "73") (name "unconnected-(IC1A-PB11-Pad22)") (class "Default")
      (node (ref "IC1") (pin "22") (pinfunction "PB11_22") (pintype "bidirectional"))
    )
    (net (code "74") (name "unconnected-(IC1A-PB12-Pad25)") (class "Default")
      (node (ref "IC1") (pin "25") (pinfunction "PB12_25") (pintype "bidirectional"))
    )
    (net (code "75") (name "unconnected-(IC1A-PB13-Pad26)") (class "Default")
      (node (ref "IC1") (pin "26") (pinfunction "PB13_26") (pintype "bidirectional"))
    )
    (net (code "76") (name "unconnected-(IC1A-PB14-Pad27)") (class "Default")
      (node (ref "IC1") (pin "27") (pinfunction "PB14_27") (pintype "bidirectional"))
    )
    (net (code "77") (name "unconnected-(IC1A-PB15-Pad28)") (class "Default")
      (node (ref "IC1") (pin "28") (pinfunction "PB15_28") (pintype "bidirectional"))
    )
    (net (code "78") (name "unconnected-(IC1A-PC15-Pad4)") (class "Default")
      (node (ref "IC1") (pin "4") (pinfunction "PC15_4") (pintype "bidirectional"))
    )
    (net (code "79") (name "unconnected-(U$1-PadEN)") (class "Default")
      (node (ref "U$1") (pin "EN") (pinfunction "EN_EN") (pintype "bidirectional"))
    )
  )
)
